# 181031_Schematic.net
KiCad netlist of a schematic drawn in Altium Designer
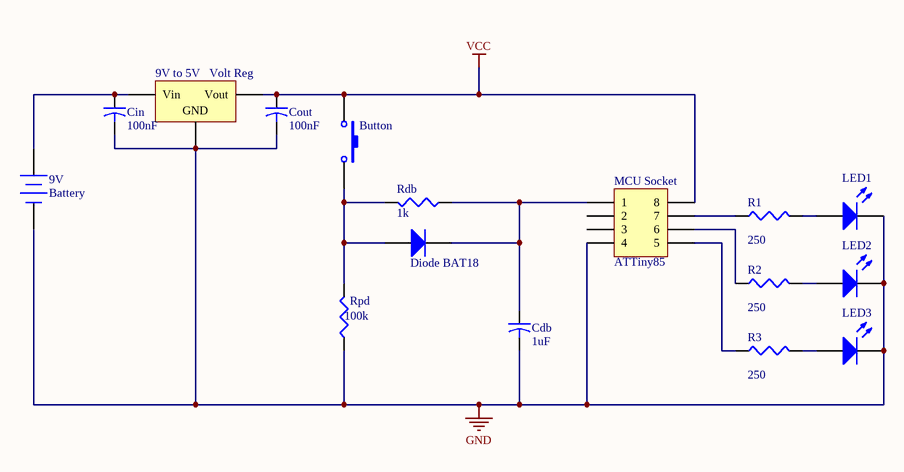
[diagram p0: 181031 Schematic.SchDoc]

(export (version "E")
  (design (tool "Eeschema 10.0.6"))
  (components
    (comp (ref "9V")
      (value "Battery")
      (footprint "BAT-2")
      (description "Multicell Battery")
      (fields (field (name "PUBLISHER") "Altium Limited"))
      (libsource (lib "Miscellaneous Devices") (part "Battery"))
    )
    (comp (ref "9V to 5V")
      (value "Volt Reg")
      (footprint "D2PAK_N")
      (description "Voltage Regulator")
      (fields (field (name "PUBLISHER") "Altium Limited"))
      (libsource (lib "Miscellaneous Devices") (part "Volt Reg"))
    )
    (comp (ref "Button")
      (value "~")
      (footprint "SPST-2")
      (description "Switch")
      (fields (field (name "PUBLISHER") "Altium Limited"))
      (libsource (lib "Miscellaneous Devices") (part "SW-PB"))
    )
    (comp (ref "Cdb")
      (value "1uF")
      (footprint "CAPR5-4X5")
      (description "Capacitor")
      (fields (field (name "PUBLISHER") "Altium Limited"))
      (libsource (lib "Miscellaneous Devices") (part "Cap2"))
    )
    (comp (ref "Cin")
      (value "100nF")
      (footprint "CAPR5-4X5")
      (description "Capacitor")
      (fields (field (name "Comment") "Cap2") (field (name "PUBLISHER") "Altium Limited"))
      (libsource (lib "Miscellaneous Devices") (part "Cap2"))
    )
    (comp (ref "Cout")
      (value "100nF")
      (footprint "CAPR5-4X5")
      (description "Capacitor")
      (fields (field (name "Comment") "10pF") (field (name "PUBLISHER") "Altium Limited"))
      (libsource (lib "Miscellaneous Devices") (part "Cap2"))
    )
    (comp (ref "D")
      (value "Diode BAT18")
      (footprint "SOT-23_N")
      (description "Low-Loss RF Switching Diode")
      (fields (field (name "PUBLISHER") "Altium Limited"))
      (libsource (lib "Miscellaneous Devices") (part "Diode BAT18"))
    )
    (comp (ref "LED1")
      (value "1")
      (footprint "LED-1")
      (description "Typical RED GaAs LED")
      (fields (field (name "PUBLISHER") "Altium Limited"))
      (libsource (lib "Miscellaneous Devices") (part "LED1"))
    )
    (comp (ref "LED2")
      (value "LED1")
      (footprint "LED-1")
      (description "Typical RED GaAs LED")
      (fields (field (name "PUBLISHER") "Altium Limited"))
      (libsource (lib "Miscellaneous Devices") (part "LED1"))
    )
    (comp (ref "LED3")
      (value "LED1")
      (footprint "LED-1")
      (description "Typical RED GaAs LED")
      (fields (field (name "PUBLISHER") "Altium Limited"))
      (libsource (lib "Miscellaneous Devices") (part "LED1"))
    )
    (comp (ref "MCU Socket")
      (value "ATTiny85")
      (footprint "HDR2X4_CEN")
      (description "Header, 4-Pin, Dual row")
      (fields (field (name "PUBLISHER") "Altium Limited"))
      (libsource (lib "Miscellaneous Connectors") (part "Header 4X2A"))
    )
    (comp (ref "R1")
      (value "250")
      (footprint "J1-0603")
      (description "Resistor")
      (fields (field (name "PUBLISHER") "Altium Limited"))
      (libsource (lib "Miscellaneous Devices") (part "Res3"))
    )
    (comp (ref "R2")
      (value "250")
      (footprint "J1-0603")
      (description "Resistor")
      (fields (field (name "PUBLISHER") "Altium Limited"))
      (libsource (lib "Miscellaneous Devices") (part "Res3"))
    )
    (comp (ref "R3")
      (value "250")
      (footprint "J1-0603")
      (description "Resistor")
      (fields (field (name "PUBLISHER") "Altium Limited"))
      (libsource (lib "Miscellaneous Devices") (part "Res3"))
    )
    (comp (ref "Rdb")
      (value "1k")
      (footprint "J1-0603")
      (description "Resistor")
      (fields (field (name "Comment") "Debounce") (field (name "PUBLISHER") "Altium Limited"))
      (libsource (lib "Miscellaneous Devices") (part "Res3"))
    )
    (comp (ref "Rpd")
      (value "100k")
      (footprint "J1-0603")
      (description "Resistor")
      (fields (field (name "PUBLISHER") "Altium Limited"))
      (libsource (lib "Miscellaneous Devices") (part "Res3"))
    )
  )
  (nets
    (net (code "1") (name "GND") (class "Default")
      (node (ref "9V") (pin "2") (pinfunction "-_2") (pintype "passive"))
      (node (ref "9V to 5V") (pin "2") (pinfunction "GND_2") (pintype "passive"))
      (node (ref "Cdb") (pin "2") (pinfunction "2_2") (pintype "passive"))
      (node (ref "Cin") (pin "2") (pinfunction "2_2") (pintype "passive"))
      (node (ref "Cout") (pin "2") (pinfunction "2_2") (pintype "passive"))
      (node (ref "LED1") (pin "2") (pinfunction "K_2") (pintype "passive"))
      (node (ref "LED2") (pin "2") (pinfunction "K_2") (pintype "passive"))
      (node (ref "LED3") (pin "2") (pinfunction "K_2") (pintype "passive"))
      (node (ref "MCU Socket") (pin "4") (pinfunction "4_4") (pintype "passive"))
      (node (ref "Rpd") (pin "1") (pinfunction "1_1") (pintype "passive"))
    )
    (net (code "2") (name "Net-(9V to 5V-Vin)") (class "Default")
      (node (ref "9V") (pin "1") (pinfunction "+_1") (pintype "passive"))
      (node (ref "9V to 5V") (pin "1") (pinfunction "Vin_1") (pintype "passive"))
      (node (ref "Cin") (pin "1") (pinfunction "1_1") (pintype "passive"))
    )
    (net (code "3") (name "Net-(D-A)") (class "Default")
      (node (ref "Button") (pin "2") (pinfunction "2_2") (pintype "passive"))
      (node (ref "D") (pin "1") (pinfunction "A_1") (pintype "passive"))
      (node (ref "Rdb") (pin "2") (pinfunction "2_2") (pintype "passive"))
      (node (ref "Rpd") (pin "2") (pinfunction "2_2") (pintype "passive"))
    )
    (net (code "4") (name "Net-(D-K)") (class "Default")
      (node (ref "Cdb") (pin "1") (pinfunction "1_1") (pintype "passive"))
      (node (ref "D") (pin "3") (pinfunction "K_3") (pintype "passive"))
      (node (ref "MCU Socket") (pin "1") (pinfunction "1_1") (pintype "passive"))
      (node (ref "Rdb") (pin "1") (pinfunction "1_1") (pintype "passive"))
    )
    (net (code "5") (name "Net-(LED1-A)") (class "Default")
      (node (ref "LED1") (pin "1") (pinfunction "A_1") (pintype "passive"))
      (node (ref "R1") (pin "2") (pinfunction "2_2") (pintype "passive"))
    )
    (net (code "6") (name "Net-(LED2-A)") (class "Default")
      (node (ref "LED2") (pin "1") (pinfunction "A_1") (pintype "passive"))
      (node (ref "R2") (pin "2") (pinfunction "2_2") (pintype "passive"))
    )
    (net (code "7") (name "Net-(LED3-A)") (class "Default")
      (node (ref "LED3") (pin "1") (pinfunction "A_1") (pintype "passive"))
      (node (ref "R3") (pin "2") (pinfunction "2_2") (pintype "passive"))
    )
    (net (code "8") (name "Net-(MCU Socket-5)") (class "Default")
      (node (ref "MCU Socket") (pin "8") (pinfunction "5_8") (pintype "passive"))
      (node (ref "R3") (pin "1") (pinfunction "1_1") (pintype "passive"))
    )
    (net (code "9") (name "Net-(MCU Socket-6)") (class "Default")
      (node (ref "MCU Socket") (pin "7") (pinfunction "6_7") (pintype "passive"))
      (node (ref "R2") (pin "1") (pinfunction "1_1") (pintype "passive"))
    )
    (net (code "10") (name "Net-(MCU Socket-7)") (class "Default")
      (node (ref "MCU Socket") (pin "6") (pinfunction "7_6") (pintype "passive"))
      (node (ref "R1") (pin "1") (pinfunction "1_1") (pintype "passive"))
    )
    (net (code "11") (name "VCC") (class "Default")
      (node (ref "9V to 5V") (pin "3") (pinfunction "Vout_3") (pintype "passive"))
      (node (ref "Button") (pin "1") (pinfunction "1_1") (pintype "passive"))
      (node (ref "Cout") (pin "1") (pinfunction "1_1") (pintype "passive"))
      (node (ref "MCU Socket") (pin "5") (pinfunction "8_5") (pintype "passive"))
    )
    (net (code "12") (name "unconnected-(MCU Socket-Pad2)") (class "Default")
      (node (ref "MCU Socket") (pin "2") (pinfunction "2_2") (pintype "passive"))
    )
    (net (code "13") (name "unconnected-(MCU Socket-Pad3)") (class "Default")
      (node (ref "MCU Socket") (pin "3") (pinfunction "3_3") (pintype "passive"))
    )
  )
)
